# Top_board.net
KiCad netlist of a schematic drawn in EAGLE
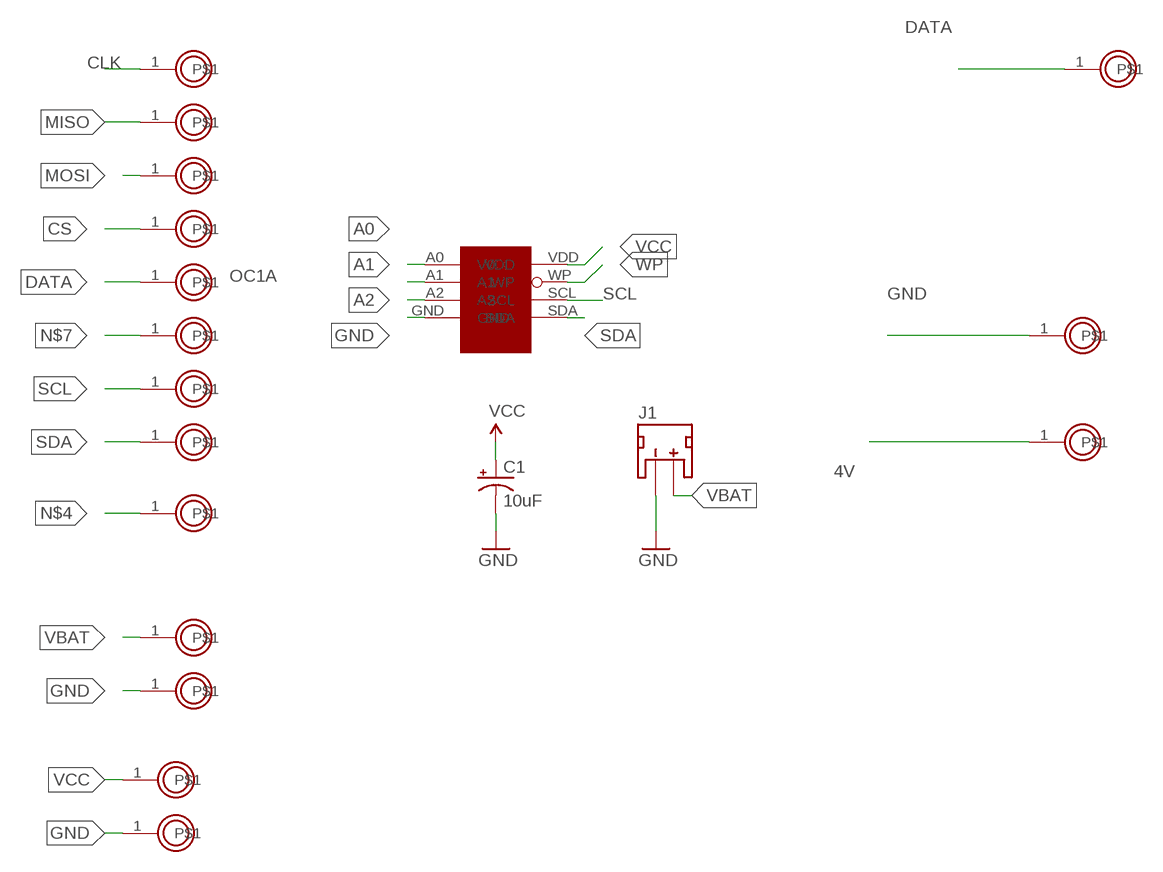
[diagram p0: schematic, sheet 1]

(export (version "E")
  (design (tool "Eeschema 10.0.6"))
  (components
    (comp (ref "0")
      (value "PROTO_POINT")
      (footprint "eagle-import:1X01")
      (libsource (lib "eagle-import") (part "PROTO_POINT"))
    )
    (comp (ref "1")
      (value "PROTO_POINT")
      (footprint "eagle-import:1X01")
      (libsource (lib "eagle-import") (part "PROTO_POINT"))
    )
    (comp (ref "2")
      (value "PROTO_POINT")
      (footprint "eagle-import:1X01")
      (libsource (lib "eagle-import") (part "PROTO_POINT"))
    )
    (comp (ref "3")
      (value "PROTO_POINT")
      (footprint "eagle-import:1X01")
      (libsource (lib "eagle-import") (part "PROTO_POINT"))
    )
    (comp (ref "4")
      (value "PROTO_POINT")
      (footprint "eagle-import:1X01")
      (libsource (lib "eagle-import") (part "PROTO_POINT"))
    )
    (comp (ref "4V")
      (value "PROTO_POINT")
      (footprint "eagle-import:1X01")
      (libsource (lib "eagle-import") (part "PROTO_POINT"))
    )
    (comp (ref "5")
      (value "PROTO_POINT")
      (footprint "eagle-import:1X01")
      (libsource (lib "eagle-import") (part "PROTO_POINT"))
    )
    (comp (ref "A0")
      (value "PROTO_POINT")
      (footprint "eagle-import:1X01")
      (libsource (lib "eagle-import") (part "PROTO_POINT"))
    )
    (comp (ref "A1")
      (value "PROTO_POINT")
      (footprint "eagle-import:1X01")
      (libsource (lib "eagle-import") (part "PROTO_POINT"))
    )
    (comp (ref "BAT")
      (value "PROTO_POINT")
      (footprint "eagle-import:1X01")
      (libsource (lib "eagle-import") (part "PROTO_POINT"))
    )
    (comp (ref "C1")
      (value "10uF")
      (footprint "eagle-import:EIA3216")
      (libsource (lib "eagle-import") (part "10UF-16V-10%(TANT)"))
    )
    (comp (ref "DATA")
      (value "PROTO_POINT")
      (footprint "eagle-import:1X01")
      (libsource (lib "eagle-import") (part "PROTO_POINT"))
    )
    (comp (ref "FRAM")
      (value "MB85RC256V")
      (footprint "eagle-import:SO08")
      (libsource (lib "eagle-import") (part "MB85RC256VMB85RC256V"))
    )
    (comp (ref "GND@1")
      (value "PROTO_POINT")
      (footprint "eagle-import:1X01")
      (libsource (lib "eagle-import") (part "PROTO_POINT"))
    )
    (comp (ref "GND@2")
      (value "PROTO_POINT")
      (footprint "eagle-import:1X01")
      (libsource (lib "eagle-import") (part "PROTO_POINT"))
    )
    (comp (ref "GND@3")
      (value "PROTO_POINT")
      (footprint "eagle-import:1X01")
      (libsource (lib "eagle-import") (part "PROTO_POINT"))
    )
    (comp (ref "J1")
      (value "JST_2MM_MALE")
      (footprint "eagle-import:JST-2-SMD")
      (libsource (lib "eagle-import") (part "JST_2MM_MALE"))
    )
    (comp (ref "RESET")
      (value "PROTO_POINT")
      (footprint "eagle-import:1X01")
      (libsource (lib "eagle-import") (part "PROTO_POINT"))
    )
    (comp (ref "VCC")
      (value "PROTO_POINT")
      (footprint "eagle-import:1X01")
      (libsource (lib "eagle-import") (part "PROTO_POINT"))
    )
  )
  (nets
    (net (code "1") (name "/4V") (class "Default")
      (node (ref "4V") (pin "1") (pinfunction "P$1_1") (pintype "bidirectional"))
    )
    (net (code "2") (name "/CLK") (class "Default")
      (node (ref "5") (pin "1") (pinfunction "P$1_1") (pintype "bidirectional"))
    )
    (net (code "3") (name "A0") (class "Default")
      (node (ref "FRAM") (pin "A0") (pinfunction "V0_A0") (pintype "input"))
    )
    (net (code "4") (name "A1") (class "Default")
      (node (ref "FRAM") (pin "A1") (pinfunction "A1_A1") (pintype "input"))
    )
    (net (code "5") (name "A2") (class "Default")
      (node (ref "FRAM") (pin "A2") (pinfunction "A2_A2") (pintype "input"))
    )
    (net (code "6") (name "CS") (class "Default")
      (node (ref "2") (pin "1") (pinfunction "P$1_1") (pintype "bidirectional"))
    )
    (net (code "7") (name "DATA") (class "Default")
      (node (ref "1") (pin "1") (pinfunction "P$1_1") (pintype "bidirectional"))
      (node (ref "DATA") (pin "1") (pinfunction "P$1_1") (pintype "bidirectional"))
    )
    (net (code "8") (name "GND") (class "Default")
      (node (ref "C1") (pin "C") (pinfunction "-_C") (pintype "passive"))
      (node (ref "FRAM") (pin "GND") (pinfunction "GND_GND") (pintype "power_in"))
      (node (ref "GND@1") (pin "1") (pinfunction "P$1_1") (pintype "bidirectional"))
      (node (ref "GND@2") (pin "1") (pinfunction "P$1_1") (pintype "bidirectional"))
      (node (ref "GND@3") (pin "1") (pinfunction "P$1_1") (pintype "bidirectional"))
      (node (ref "J1") (pin "1") (pinfunction "-_1") (pintype "bidirectional"))
    )
    (net (code "9") (name "MISO") (class "Default")
      (node (ref "4") (pin "1") (pinfunction "P$1_1") (pintype "bidirectional"))
    )
    (net (code "10") (name "MOSI") (class "Default")
      (node (ref "3") (pin "1") (pinfunction "P$1_1") (pintype "bidirectional"))
    )
    (net (code "11") (name "N$4") (class "Default")
      (node (ref "RESET") (pin "1") (pinfunction "P$1_1") (pintype "bidirectional"))
    )
    (net (code "12") (name "N$7") (class "Default")
      (node (ref "0") (pin "1") (pinfunction "P$1_1") (pintype "bidirectional"))
    )
    (net (code "13") (name "SCL") (class "Default")
      (node (ref "A1") (pin "1") (pinfunction "P$1_1") (pintype "bidirectional"))
      (node (ref "FRAM") (pin "SCL") (pinfunction "SCL_SCL") (pintype "output"))
    )
    (net (code "14") (name "SDA") (class "Default")
      (node (ref "A0") (pin "1") (pinfunction "P$1_1") (pintype "bidirectional"))
      (node (ref "FRAM") (pin "SDA") (pinfunction "SDA_SDA") (pintype "bidirectional"))
    )
    (net (code "15") (name "VBAT") (class "Default")
      (node (ref "BAT") (pin "1") (pinfunction "P$1_1") (pintype "bidirectional"))
      (node (ref "J1") (pin "2") (pinfunction "+_2") (pintype "bidirectional"))
    )
    (net (code "16") (name "VCC") (class "Default")
      (node (ref "C1") (pin "A") (pinfunction "+_A") (pintype "passive"))
      (node (ref "FRAM") (pin "VDD") (pinfunction "VDD_VDD") (pintype "power_in"))
      (node (ref "VCC") (pin "1") (pinfunction "P$1_1") (pintype "bidirectional"))
    )
    (net (code "17") (name "WP") (class "Default")
      (node (ref "FRAM") (pin "WP") (pinfunction "WP_WP") (pintype "input"))
    )
    (net (code "18") (name "unconnected-(J1-PAD1-PadNC1)") (class "Default")
      (node (ref "J1") (pin "NC1") (pinfunction "PAD1_NC1") (pintype "bidirectional"))
    )
    (net (code "19") (name "unconnected-(J1-PAD2-PadNC2)") (class "Default")
      (node (ref "J1") (pin "NC2") (pinfunction "PAD2_NC2") (pintype "bidirectional"))
    )
  )
)
